# Backplane_LED_s.net
KiCad netlist of a schematic drawn in Altium Designer
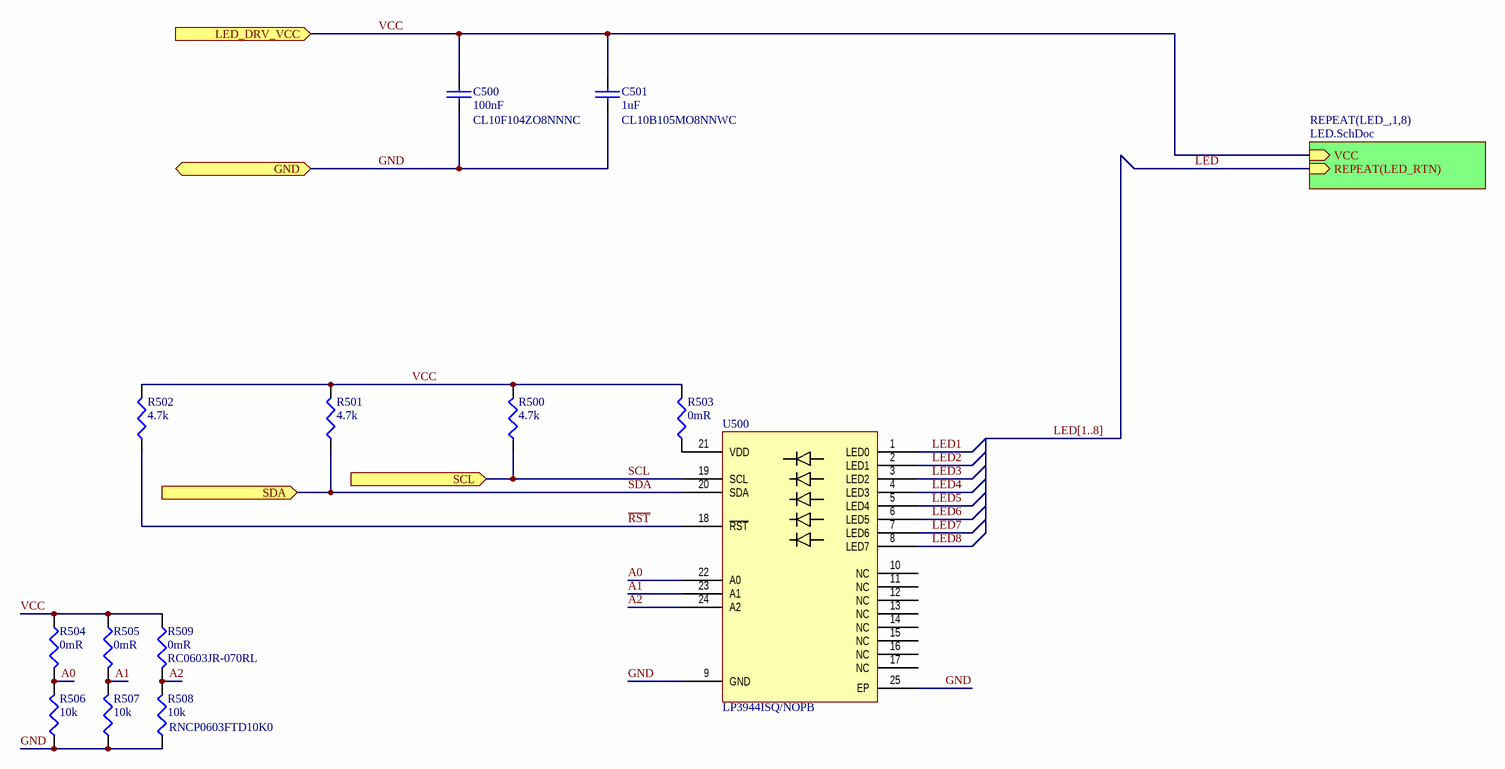
[diagram p0: Backplane LED's.SchDoc]

(export (version "E")
  (design (tool "Eeschema 10.0.6"))
  (components
    (comp (ref "C500")
      (value "100nF")
      (footprint "0603")
      (description "Cap Ceramic 0.1uF 16V Y5V -20% to 80% SMD 0603 85C Paper T/R")
      (fields (field (name "MANUFACTURER PART NUMBER 1") "CL10F104ZO8NNNC") (field (name "TOLERANCE") "80%"))
      (libsource (lib "CubeSat-Backplane") (part "CAP"))
    )
    (comp (ref "C501")
      (value "1uF")
      (footprint "0603")
      (description "CAP CER 1UF 16V X7R 0603")
      (fields (field (name "MANUFACTURER PART NUMBER 1") "CL10B105MO8NNWC") (field (name "TOLERANCE") "20%"))
      (libsource (lib "CubeSat-Backplane") (part "CAP"))
    )
    (comp (ref "R500")
      (value "4.7k")
      (footprint "RES_603")
      (description "RNCP0603FTD10K0")
      (libsource (lib "CubeSat-Backplane") (part "RES1"))
    )
    (comp (ref "R501")
      (value "4.7k")
      (footprint "RES_603")
      (description "RNCP0603FTD10K0")
      (libsource (lib "CubeSat-Backplane") (part "RES1"))
    )
    (comp (ref "R502")
      (value "4.7k")
      (footprint "RES_603")
      (description "RNCP0603FTD10K0")
      (libsource (lib "CubeSat-Backplane") (part "RES1"))
    )
    (comp (ref "R503")
      (value "0mR")
      (footprint "0603")
      (description "RES SMD 0 OHM JUMPER 1/10W 0603")
      (fields (field (name "TOLERANCE") "1%"))
      (libsource (lib "CubeSat-Backplane") (part "RES1"))
    )
    (comp (ref "R504")
      (value "0mR")
      (footprint "0603")
      (description "RES SMD 0 OHM JUMPER 1/10W 0603")
      (fields (field (name "TOLERANCE") "1%"))
      (libsource (lib "CubeSat-Backplane") (part "RES1"))
    )
    (comp (ref "R505")
      (value "0mR")
      (footprint "0603")
      (description "RES SMD 0 OHM JUMPER 1/10W 0603")
      (fields (field (name "TOLERANCE") "1%"))
      (libsource (lib "CubeSat-Backplane") (part "RES1"))
    )
    (comp (ref "R506")
      (value "10k")
      (footprint "RES_603")
      (libsource (lib "CubeSat-Backplane") (part "RES1"))
    )
    (comp (ref "R507")
      (value "10k")
      (footprint "RES_603")
      (libsource (lib "CubeSat-Backplane") (part "RES1"))
    )
    (comp (ref "R508")
      (value "10k")
      (footprint "RES_603")
      (fields (field (name "MFR. P/N") "RNCP0603FTD10K0"))
      (libsource (lib "CubeSat-Backplane") (part "RES1"))
    )
    (comp (ref "R509")
      (value "0mR")
      (footprint "0603")
      (description "RES SMD 0 OHM JUMPER 1/10W 0603")
      (fields (field (name "MANUFACTURER PART NUMBER 1") "RC0603JR-070RL") (field (name "TOLERANCE") "1%"))
      (libsource (lib "CubeSat-Backplane") (part "RES1"))
    )
    (comp (ref "U500")
      (value "LP3944ISQ/NOPB")
      (footprint "CubeSat-Backplane:LP3944ISQ/NOPB")
      (description "IC LED DRIVER PS DIM 25MA 24WQFN")
      (libsource (lib "CubeSat-Backplane") (part "LP3944ISQ/NOPB"))
    )
  )
  (nets
    (net (code "1") (name "/A0") (class "Default")
      (node (ref "R504") (pin "2") (pinfunction "2_2") (pintype "passive"))
      (node (ref "R506") (pin "2") (pinfunction "2_2") (pintype "passive"))
      (node (ref "U500") (pin "22") (pinfunction "A0_22") (pintype "passive"))
    )
    (net (code "2") (name "/A1") (class "Default")
      (node (ref "R505") (pin "2") (pinfunction "2_2") (pintype "passive"))
      (node (ref "R507") (pin "2") (pinfunction "2_2") (pintype "passive"))
      (node (ref "U500") (pin "23") (pinfunction "A1_23") (pintype "passive"))
    )
    (net (code "3") (name "/A2") (class "Default")
      (node (ref "R508") (pin "2") (pinfunction "2_2") (pintype "passive"))
      (node (ref "R509") (pin "2") (pinfunction "2_2") (pintype "passive"))
      (node (ref "U500") (pin "24") (pinfunction "A2_24") (pintype "passive"))
    )
    (net (code "4") (name "/GND") (class "Default")
      (node (ref "C500") (pin "2") (pinfunction "2_2") (pintype "passive"))
      (node (ref "C501") (pin "2") (pinfunction "2_2") (pintype "passive"))
      (node (ref "R506") (pin "1") (pinfunction "1_1") (pintype "passive"))
      (node (ref "R507") (pin "1") (pinfunction "1_1") (pintype "passive"))
      (node (ref "R508") (pin "1") (pinfunction "1_1") (pintype "passive"))
      (node (ref "U500") (pin "25") (pinfunction "EP_25") (pintype "passive"))
      (node (ref "U500") (pin "9") (pinfunction "GND_9") (pintype "passive"))
    )
    (net (code "6") (name "/LED1") (class "Default")
      (node (ref "U500") (pin "1") (pinfunction "LED0_1") (pintype "passive"))
    )
    (net (code "7") (name "/LED2") (class "Default")
      (node (ref "U500") (pin "2") (pinfunction "LED1_2") (pintype "passive"))
    )
    (net (code "8") (name "/LED3") (class "Default")
      (node (ref "U500") (pin "3") (pinfunction "LED2_3") (pintype "passive"))
    )
    (net (code "9") (name "/LED4") (class "Default")
      (node (ref "U500") (pin "4") (pinfunction "LED3_4") (pintype "passive"))
    )
    (net (code "10") (name "/LED5") (class "Default")
      (node (ref "U500") (pin "5") (pinfunction "LED4_5") (pintype "passive"))
    )
    (net (code "11") (name "/LED6") (class "Default")
      (node (ref "U500") (pin "6") (pinfunction "LED5_6") (pintype "passive"))
    )
    (net (code "12") (name "/LED7") (class "Default")
      (node (ref "U500") (pin "7") (pinfunction "LED6_7") (pintype "passive"))
    )
    (net (code "13") (name "/LED8") (class "Default")
      (node (ref "U500") (pin "8") (pinfunction "LED7_8") (pintype "passive"))
    )
    (net (code "15") (name "/SCL") (class "Default")
      (node (ref "R500") (pin "1") (pinfunction "1_1") (pintype "passive"))
      (node (ref "U500") (pin "19") (pinfunction "SCL_19") (pintype "passive"))
    )
    (net (code "16") (name "/SDA") (class "Default")
      (node (ref "R501") (pin "1") (pinfunction "1_1") (pintype "passive"))
      (node (ref "U500") (pin "20") (pinfunction "SDA_20") (pintype "passive"))
    )
    (net (code "17") (name "/VCC") (class "Default")
      (node (ref "C500") (pin "1") (pinfunction "1_1") (pintype "passive"))
      (node (ref "C501") (pin "1") (pinfunction "1_1") (pintype "passive"))
      (node (ref "R500") (pin "2") (pinfunction "2_2") (pintype "passive"))
      (node (ref "R501") (pin "2") (pinfunction "2_2") (pintype "passive"))
      (node (ref "R502") (pin "2") (pinfunction "2_2") (pintype "passive"))
      (node (ref "R503") (pin "2") (pinfunction "2_2") (pintype "passive"))
      (node (ref "R504") (pin "1") (pinfunction "1_1") (pintype "passive"))
      (node (ref "R505") (pin "1") (pinfunction "1_1") (pintype "passive"))
      (node (ref "R509") (pin "1") (pinfunction "1_1") (pintype "passive"))
    )
    (net (code "18") (name "/~{RST}") (class "Default")
      (node (ref "R502") (pin "1") (pinfunction "1_1") (pintype "passive"))
      (node (ref "U500") (pin "18") (pinfunction "~{RST}_18") (pintype "passive"))
    )
    (net (code "19") (name "Net-(U500-VDD)") (class "Default")
      (node (ref "R503") (pin "1") (pinfunction "1_1") (pintype "passive"))
      (node (ref "U500") (pin "21") (pinfunction "VDD_21") (pintype "passive"))
    )
    (net (code "20") (name "unconnected-(U500-NC-Pad10)") (class "Default")
      (node (ref "U500") (pin "10") (pinfunction "NC_10") (pintype "passive"))
    )
    (net (code "21") (name "unconnected-(U500-NC-Pad11)") (class "Default")
      (node (ref "U500") (pin "11") (pinfunction "NC_11") (pintype "passive"))
    )
    (net (code "22") (name "unconnected-(U500-NC-Pad12)") (class "Default")
      (node (ref "U500") (pin "12") (pinfunction "NC_12") (pintype "passive"))
    )
    (net (code "23") (name "unconnected-(U500-NC-Pad13)") (class "Default")
      (node (ref "U500") (pin "13") (pinfunction "NC_13") (pintype "passive"))
    )
    (net (code "24") (name "unconnected-(U500-NC-Pad14)") (class "Default")
      (node (ref "U500") (pin "14") (pinfunction "NC_14") (pintype "passive"))
    )
    (net (code "25") (name "unconnected-(U500-NC-Pad15)") (class "Default")
      (node (ref "U500") (pin "15") (pinfunction "NC_15") (pintype "passive"))
    )
    (net (code "26") (name "unconnected-(U500-NC-Pad16)") (class "Default")
      (node (ref "U500") (pin "16") (pinfunction "NC_16") (pintype "passive"))
    )
    (net (code "27") (name "unconnected-(U500-NC-Pad17)") (class "Default")
      (node (ref "U500") (pin "17") (pinfunction "NC_17") (pintype "passive"))
    )
  )
)
